# schematic.net
KiCad netlist of a schematic drawn in EAGLE
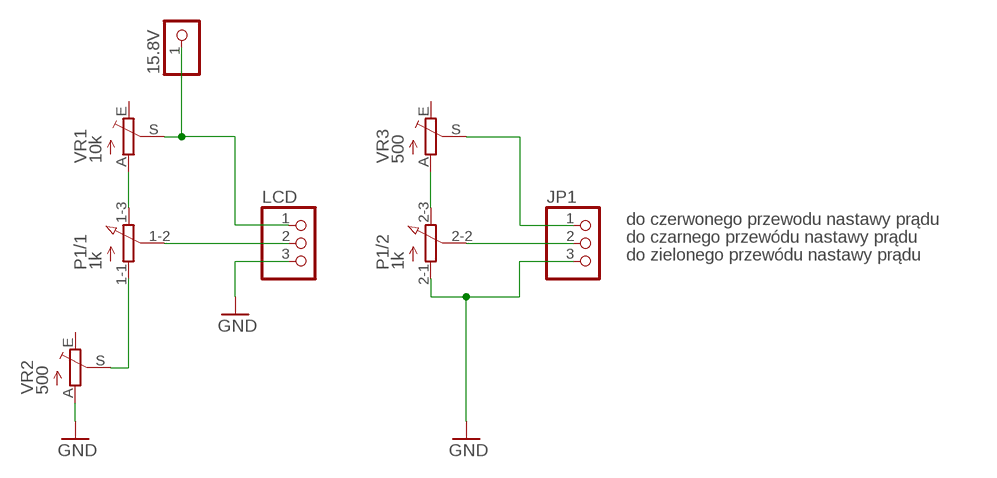
[diagram p0: schematic, sheet 1]

(export (version "E")
  (design (tool "Eeschema 10.0.6"))
  (components
    (comp (ref "15.8V")
      (value "PINHD-1X1")
      (footprint "eagle-import:1X01")
      (libsource (lib "eagle-import") (part "PINHD-1X1"))
    )
    (comp (ref "JP1")
      (value "PINHD-1X3")
      (footprint "eagle-import:1X03")
      (libsource (lib "eagle-import") (part "PINHD-1X3"))
    )
    (comp (ref "LCD")
      (value "PINHD-1X3")
      (footprint "eagle-import:1X03")
      (libsource (lib "eagle-import") (part "PINHD-1X3"))
    )
    (comp (ref "P1")
      (value "1k")
      (footprint "eagle-import:3RP_1610G")
      (libsource (lib "eagle-import") (part "3RP/1610G"))
    )
    (comp (ref "VR1")
      (value "10k")
      (footprint "eagle-import:RJ9W")
      (libsource (lib "eagle-import") (part "TRIM_EU-RJ9W"))
    )
    (comp (ref "VR2")
      (value "500")
      (footprint "eagle-import:RJ9W")
      (libsource (lib "eagle-import") (part "TRIM_EU-RJ9W"))
    )
    (comp (ref "VR3")
      (value "500")
      (footprint "eagle-import:RJ9W")
      (libsource (lib "eagle-import") (part "TRIM_EU-RJ9W"))
    )
  )
  (nets
    (net (code "1") (name "GND") (class "Default")
      (node (ref "JP1") (pin "3") (pinfunction "3_3") (pintype "passive"))
      (node (ref "LCD") (pin "3") (pinfunction "3_3") (pintype "passive"))
      (node (ref "P1") (pin "2-1") (pinfunction "A_2-1") (pintype "passive"))
      (node (ref "VR2") (pin "A") (pinfunction "A_A") (pintype "passive"))
    )
    (net (code "2") (name "Net-(15.8V-Pad1)") (class "Default")
      (node (ref "15.8V") (pin "1") (pinfunction "1_1") (pintype "passive"))
      (node (ref "LCD") (pin "1") (pinfunction "1_1") (pintype "passive"))
      (node (ref "VR1") (pin "S") (pinfunction "S_S") (pintype "passive"))
    )
    (net (code "3") (name "Net-(JP1-Pad1)") (class "Default")
      (node (ref "JP1") (pin "1") (pinfunction "1_1") (pintype "passive"))
      (node (ref "VR3") (pin "S") (pinfunction "S_S") (pintype "passive"))
    )
    (net (code "4") (name "Net-(P1A-A)") (class "Default")
      (node (ref "P1") (pin "1-1") (pinfunction "A_1-1") (pintype "passive"))
      (node (ref "VR2") (pin "S") (pinfunction "S_S") (pintype "passive"))
    )
    (net (code "5") (name "Net-(P1A-E)") (class "Default")
      (node (ref "P1") (pin "1-3") (pinfunction "E_1-3") (pintype "passive"))
      (node (ref "VR1") (pin "A") (pinfunction "A_A") (pintype "passive"))
    )
    (net (code "6") (name "Net-(P1A-S)") (class "Default")
      (node (ref "LCD") (pin "2") (pinfunction "2_2") (pintype "passive"))
      (node (ref "P1") (pin "1-2") (pinfunction "S_1-2") (pintype "passive"))
    )
    (net (code "7") (name "Net-(P1B-E)") (class "Default")
      (node (ref "P1") (pin "2-3") (pinfunction "E_2-3") (pintype "passive"))
      (node (ref "VR3") (pin "A") (pinfunction "A_A") (pintype "passive"))
    )
    (net (code "8") (name "Net-(P1B-S)") (class "Default")
      (node (ref "JP1") (pin "2") (pinfunction "2_2") (pintype "passive"))
      (node (ref "P1") (pin "2-2") (pinfunction "S_2-2") (pintype "passive"))
    )
    (net (code "9") (name "unconnected-(VR1-PadE)") (class "Default")
      (node (ref "VR1") (pin "E") (pinfunction "E_E") (pintype "passive"))
    )
    (net (code "10") (name "unconnected-(VR2-PadE)") (class "Default")
      (node (ref "VR2") (pin "E") (pinfunction "E_E") (pintype "passive"))
    )
    (net (code "11") (name "unconnected-(VR3-PadE)") (class "Default")
      (node (ref "VR3") (pin "E") (pinfunction "E_E") (pintype "passive"))
    )
  )
)
